# TC_PCB.net
KiCad netlist of a schematic drawn in Altium Designer
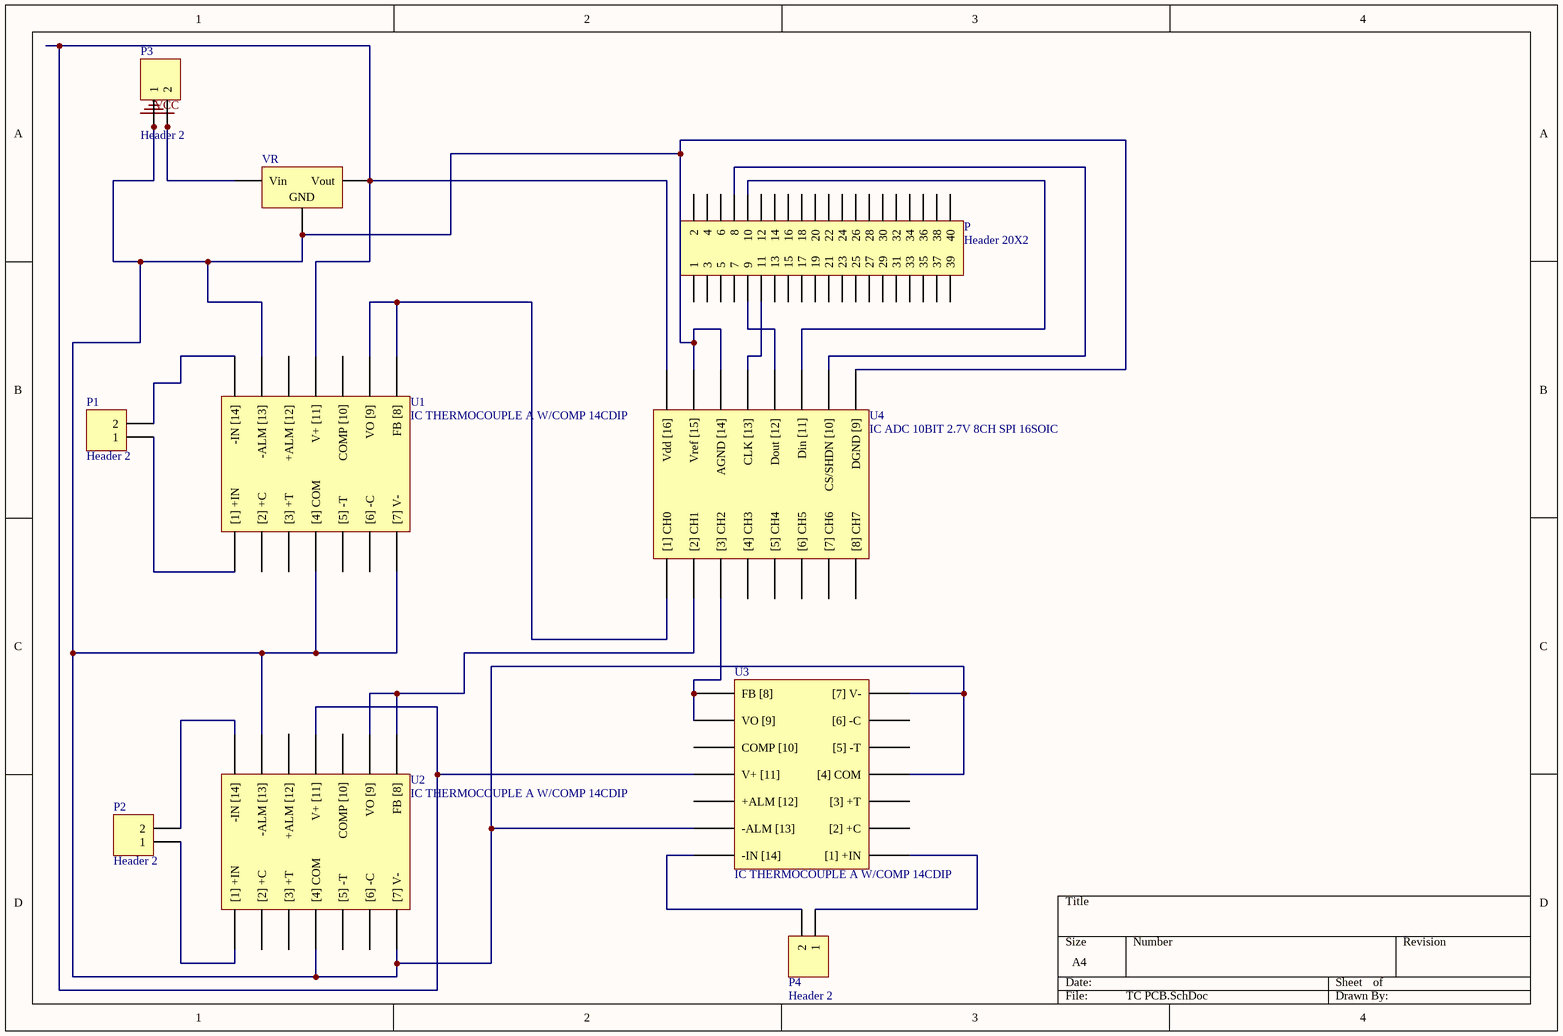
[diagram p0: TC PCB.SchDoc]

(export (version "E")
  (design (tool "Eeschema 10.0.6"))
  (components
    (comp (ref "P")
      (value "Header 20X2")
      (footprint "HDR2X20")
      (description "Header, 20-Pin, Dual row")
      (fields (field (name "PUBLISHER") "Altium Limited"))
      (libsource (lib "Miscellaneous Connectors") (part "Header 20X2"))
    )
    (comp (ref "P1")
      (value "Header 2")
      (footprint "HDR1X2")
      (description "Header, 2-Pin")
      (fields (field (name "PUBLISHER") "Altium Limited"))
      (libsource (lib "Miscellaneous Connectors") (part "Header 2"))
    )
    (comp (ref "P2")
      (value "Header 2")
      (footprint "HDR1X2")
      (description "Header, 2-Pin")
      (fields (field (name "PUBLISHER") "Altium Limited"))
      (libsource (lib "Miscellaneous Connectors") (part "Header 2"))
    )
    (comp (ref "P3")
      (value "Header 2")
      (footprint "HDR1X2")
      (description "Header, 2-Pin")
      (fields (field (name "PUBLISHER") "Altium Limited"))
      (libsource (lib "") (part "Header 2_1"))
    )
    (comp (ref "P4")
      (value "Header 2")
      (footprint "HDR1X2")
      (description "Header, 2-Pin")
      (fields (field (name "PUBLISHER") "Altium Limited"))
      (libsource (lib "") (part "Header 2_2"))
    )
    (comp (ref "U1")
      (value "IC THERMOCOUPLE A W/COMP 14CDIP")
      (footprint "IC THERMOCOUPLE A W/COMP 14CDIP")
      (libsource (lib "Main_Parts_Library") (part "IC THERMOCOUPLE A W/COMP 14CDIP"))
    )
    (comp (ref "U2")
      (value "IC THERMOCOUPLE A W/COMP 14CDIP")
      (footprint "IC THERMOCOUPLE A W/COMP 14CDIP")
      (libsource (lib "Main_Parts_Library") (part "IC THERMOCOUPLE A W/COMP 14CDIP"))
    )
    (comp (ref "U3")
      (value "IC THERMOCOUPLE A W/COMP 14CDIP")
      (footprint "IC THERMOCOUPLE A W/COMP 14CDIP")
      (libsource (lib "") (part "IC THERMOCOUPLE A W/COMP 14CDIP_1"))
    )
    (comp (ref "U4")
      (value "IC ADC 10BIT 2.7V 8CH SPI 16SOIC")
      (footprint "IC ADC 10BIT 2.7V 8CH SPI 16SOIC")
      (libsource (lib "Main_Parts_Library") (part "IC ADC 10BIT 2.7V 8CH SPI 16SOIC"))
    )
    (comp (ref "VR")
      (value "Volt Reg")
      (footprint "D2PAK_N")
      (description "Voltage Regulator")
      (fields (field (name "PUBLISHER") "Altium Limited"))
      (libsource (lib "Miscellaneous Devices") (part "Volt Reg"))
    )
  )
  (nets
    (net (code "1") (name "GND") (class "Default")
      (node (ref "P3") (pin "1") (pinfunction "1_1") (pintype "passive"))
      (node (ref "U1") (pin "13") (pinfunction "-ALM_[13]_13") (pintype "passive"))
      (node (ref "U1") (pin "4") (pinfunction "[4]_COM_4") (pintype "passive"))
      (node (ref "U1") (pin "7") (pinfunction "[7]_V-_7") (pintype "passive"))
      (node (ref "U2") (pin "13") (pinfunction "-ALM_[13]_13") (pintype "passive"))
      (node (ref "U2") (pin "4") (pinfunction "[4]_COM_4") (pintype "passive"))
      (node (ref "U2") (pin "7") (pinfunction "[7]_V-_7") (pintype "passive"))
      (node (ref "U3") (pin "13") (pinfunction "-ALM_[13]_13") (pintype "passive"))
      (node (ref "U3") (pin "4") (pinfunction "[4]_COM_4") (pintype "passive"))
      (node (ref "U3") (pin "7") (pinfunction "[7]_V-_7") (pintype "passive"))
      (node (ref "U4") (pin "14") (pinfunction "AGND_[14]_14") (pintype "passive"))
      (node (ref "U4") (pin "15") (pinfunction "Vref_[15]_15") (pintype "passive"))
      (node (ref "U4") (pin "9") (pinfunction "DGND_[9]_9") (pintype "passive"))
      (node (ref "VR") (pin "2") (pinfunction "GND_2") (pintype "passive"))
    )
    (net (code "2") (name "Net-(U1--IN_[14])") (class "Default")
      (node (ref "P1") (pin "2") (pinfunction "2_2") (pintype "passive"))
      (node (ref "U1") (pin "14") (pinfunction "-IN_[14]_14") (pintype "passive"))
    )
    (net (code "3") (name "Net-(U1-FB_[8])") (class "Default")
      (node (ref "U1") (pin "8") (pinfunction "FB_[8]_8") (pintype "passive"))
      (node (ref "U1") (pin "9") (pinfunction "VO_[9]_9") (pintype "passive"))
      (node (ref "U4") (pin "1") (pinfunction "[1]_CH0_1") (pintype "passive"))
    )
    (net (code "4") (name "Net-(U1-V+_[11])") (class "Default")
      (node (ref "U1") (pin "11") (pinfunction "V+_[11]_11") (pintype "passive"))
      (node (ref "U2") (pin "11") (pinfunction "V+_[11]_11") (pintype "passive"))
      (node (ref "U3") (pin "11") (pinfunction "V+_[11]_11") (pintype "passive"))
      (node (ref "U4") (pin "16") (pinfunction "Vdd_[16]_16") (pintype "passive"))
      (node (ref "VR") (pin "3") (pinfunction "Vout_3") (pintype "passive"))
    )
    (net (code "5") (name "Net-(U1-[1]_+IN)") (class "Default")
      (node (ref "P1") (pin "1") (pinfunction "1_1") (pintype "passive"))
      (node (ref "U1") (pin "1") (pinfunction "[1]_+IN_1") (pintype "passive"))
    )
    (net (code "6") (name "Net-(U2--IN_[14])") (class "Default")
      (node (ref "P2") (pin "2") (pinfunction "2_2") (pintype "passive"))
      (node (ref "U2") (pin "14") (pinfunction "-IN_[14]_14") (pintype "passive"))
    )
    (net (code "7") (name "Net-(U2-FB_[8])") (class "Default")
      (node (ref "U2") (pin "8") (pinfunction "FB_[8]_8") (pintype "passive"))
      (node (ref "U2") (pin "9") (pinfunction "VO_[9]_9") (pintype "passive"))
      (node (ref "U4") (pin "2") (pinfunction "[2]_CH1_2") (pintype "passive"))
    )
    (net (code "8") (name "Net-(U2-[1]_+IN)") (class "Default")
      (node (ref "P2") (pin "1") (pinfunction "1_1") (pintype "passive"))
      (node (ref "U2") (pin "1") (pinfunction "[1]_+IN_1") (pintype "passive"))
    )
    (net (code "9") (name "Net-(U3--IN_[14])") (class "Default")
      (node (ref "P4") (pin "2") (pinfunction "2_2") (pintype "passive"))
      (node (ref "U3") (pin "14") (pinfunction "-IN_[14]_14") (pintype "passive"))
    )
    (net (code "10") (name "Net-(U3-FB_[8])") (class "Default")
      (node (ref "U3") (pin "8") (pinfunction "FB_[8]_8") (pintype "passive"))
      (node (ref "U3") (pin "9") (pinfunction "VO_[9]_9") (pintype "passive"))
      (node (ref "U4") (pin "3") (pinfunction "[3]_CH2_3") (pintype "passive"))
    )
    (net (code "11") (name "Net-(U3-[1]_+IN)") (class "Default")
      (node (ref "P4") (pin "1") (pinfunction "1_1") (pintype "passive"))
      (node (ref "U3") (pin "1") (pinfunction "[1]_+IN_1") (pintype "passive"))
    )
    (net (code "12") (name "Net-(U4-CLK_[13])") (class "Default")
      (node (ref "P") (pin "11") (pinfunction "11_11") (pintype "passive"))
      (node (ref "U4") (pin "13") (pinfunction "CLK_[13]_13") (pintype "passive"))
    )
    (net (code "13") (name "Net-(U4-CS{slash}SHDN_[10])") (class "Default")
      (node (ref "P") (pin "8") (pinfunction "8_8") (pintype "passive"))
      (node (ref "U4") (pin "10") (pinfunction "CS/SHDN_[10]_10") (pintype "passive"))
    )
    (net (code "14") (name "Net-(U4-Din_[11])") (class "Default")
      (node (ref "P") (pin "10") (pinfunction "10_10") (pintype "passive"))
      (node (ref "U4") (pin "11") (pinfunction "Din_[11]_11") (pintype "passive"))
    )
    (net (code "15") (name "Net-(U4-Dout_[12])") (class "Default")
      (node (ref "P") (pin "9") (pinfunction "9_9") (pintype "passive"))
      (node (ref "U4") (pin "12") (pinfunction "Dout_[12]_12") (pintype "passive"))
    )
    (net (code "16") (name "VCC") (class "Default")
      (node (ref "P3") (pin "2") (pinfunction "2_2") (pintype "passive"))
      (node (ref "VR") (pin "1") (pinfunction "Vin_1") (pintype "passive"))
    )
    (net (code "17") (name "unconnected-(P-Pad1)") (class "Default")
      (node (ref "P") (pin "1") (pinfunction "1_1") (pintype "passive"))
    )
    (net (code "18") (name "unconnected-(P-Pad2)") (class "Default")
      (node (ref "P") (pin "2") (pinfunction "2_2") (pintype "passive"))
    )
    (net (code "19") (name "unconnected-(P-Pad3)") (class "Default")
      (node (ref "P") (pin "3") (pinfunction "3_3") (pintype "passive"))
    )
    (net (code "20") (name "unconnected-(P-Pad4)") (class "Default")
      (node (ref "P") (pin "4") (pinfunction "4_4") (pintype "passive"))
    )
    (net (code "21") (name "unconnected-(P-Pad5)") (class "Default")
      (node (ref "P") (pin "5") (pinfunction "5_5") (pintype "passive"))
    )
    (net (code "22") (name "unconnected-(P-Pad6)") (class "Default")
      (node (ref "P") (pin "6") (pinfunction "6_6") (pintype "passive"))
    )
    (net (code "23") (name "unconnected-(P-Pad7)") (class "Default")
      (node (ref "P") (pin "7") (pinfunction "7_7") (pintype "passive"))
    )
    (net (code "24") (name "unconnected-(P-Pad12)") (class "Default")
      (node (ref "P") (pin "12") (pinfunction "12_12") (pintype "passive"))
    )
    (net (code "25") (name "unconnected-(P-Pad13)") (class "Default")
      (node (ref "P") (pin "13") (pinfunction "13_13") (pintype "passive"))
    )
    (net (code "26") (name "unconnected-(P-Pad14)") (class "Default")
      (node (ref "P") (pin "14") (pinfunction "14_14") (pintype "passive"))
    )
    (net (code "27") (name "unconnected-(P-Pad15)") (class "Default")
      (node (ref "P") (pin "15") (pinfunction "15_15") (pintype "passive"))
    )
    (net (code "28") (name "unconnected-(P-Pad16)") (class "Default")
      (node (ref "P") (pin "16") (pinfunction "16_16") (pintype "passive"))
    )
    (net (code "29") (name "unconnected-(P-Pad17)") (class "Default")
      (node (ref "P") (pin "17") (pinfunction "17_17") (pintype "passive"))
    )
    (net (code "30") (name "unconnected-(P-Pad18)") (class "Default")
      (node (ref "P") (pin "18") (pinfunction "18_18") (pintype "passive"))
    )
    (net (code "31") (name "unconnected-(P-Pad19)") (class "Default")
      (node (ref "P") (pin "19") (pinfunction "19_19") (pintype "passive"))
    )
    (net (code "32") (name "unconnected-(P-Pad20)") (class "Default")
      (node (ref "P") (pin "20") (pinfunction "20_20") (pintype "passive"))
    )
    (net (code "33") (name "unconnected-(P-Pad21)") (class "Default")
      (node (ref "P") (pin "21") (pinfunction "21_21") (pintype "passive"))
    )
    (net (code "34") (name "unconnected-(P-Pad22)") (class "Default")
      (node (ref "P") (pin "22") (pinfunction "22_22") (pintype "passive"))
    )
    (net (code "35") (name "unconnected-(P-Pad23)") (class "Default")
      (node (ref "P") (pin "23") (pinfunction "23_23") (pintype "passive"))
    )
    (net (code "36") (name "unconnected-(P-Pad24)") (class "Default")
      (node (ref "P") (pin "24") (pinfunction "24_24") (pintype "passive"))
    )
    (net (code "37") (name "unconnected-(P-Pad25)") (class "Default")
      (node (ref "P") (pin "25") (pinfunction "25_25") (pintype "passive"))
    )
    (net (code "38") (name "unconnected-(P-Pad26)") (class "Default")
      (node (ref "P") (pin "26") (pinfunction "26_26") (pintype "passive"))
    )
    (net (code "39") (name "unconnected-(P-Pad27)") (class "Default")
      (node (ref "P") (pin "27") (pinfunction "27_27") (pintype "passive"))
    )
    (net (code "40") (name "unconnected-(P-Pad28)") (class "Default")
      (node (ref "P") (pin "28") (pinfunction "28_28") (pintype "passive"))
    )
    (net (code "41") (name "unconnected-(P-Pad29)") (class "Default")
      (node (ref "P") (pin "29") (pinfunction "29_29") (pintype "passive"))
    )
    (net (code "42") (name "unconnected-(P-Pad30)") (class "Default")
      (node (ref "P") (pin "30") (pinfunction "30_30") (pintype "passive"))
    )
    (net (code "43") (name "unconnected-(P-Pad31)") (class "Default")
      (node (ref "P") (pin "31") (pinfunction "31_31") (pintype "passive"))
    )
    (net (code "44") (name "unconnected-(P-Pad32)") (class "Default")
      (node (ref "P") (pin "32") (pinfunction "32_32") (pintype "passive"))
    )
    (net (code "45") (name "unconnected-(P-Pad33)") (class "Default")
      (node (ref "P") (pin "33") (pinfunction "33_33") (pintype "passive"))
    )
    (net (code "46") (name "unconnected-(P-Pad34)") (class "Default")
      (node (ref "P") (pin "34") (pinfunction "34_34") (pintype "passive"))
    )
    (net (code "47") (name "unconnected-(P-Pad35)") (class "Default")
      (node (ref "P") (pin "35") (pinfunction "35_35") (pintype "passive"))
    )
    (net (code "48") (name "unconnected-(P-Pad36)") (class "Default")
      (node (ref "P") (pin "36") (pinfunction "36_36") (pintype "passive"))
    )
    (net (code "49") (name "unconnected-(P-Pad37)") (class "Default")
      (node (ref "P") (pin "37") (pinfunction "37_37") (pintype "passive"))
    )
    (net (code "50") (name "unconnected-(P-Pad38)") (class "Default")
      (node (ref "P") (pin "38") (pinfunction "38_38") (pintype "passive"))
    )
    (net (code "51") (name "unconnected-(P-Pad39)") (class "Default")
      (node (ref "P") (pin "39") (pinfunction "39_39") (pintype "passive"))
    )
    (net (code "52") (name "unconnected-(P-Pad40)") (class "Default")
      (node (ref "P") (pin "40") (pinfunction "40_40") (pintype "passive"))
    )
    (net (code "53") (name "unconnected-(U1-+ALM_[12]-Pad12)") (class "Default")
      (node (ref "U1") (pin "12") (pinfunction "+ALM_[12]_12") (pintype "passive"))
    )
    (net (code "54") (name "unconnected-(U1-COMP_[10]-Pad10)") (class "Default")
      (node (ref "U1") (pin "10") (pinfunction "COMP_[10]_10") (pintype "passive"))
    )
    (net (code "55") (name "unconnected-(U1-[2]_+C-Pad2)") (class "Default")
      (node (ref "U1") (pin "2") (pinfunction "[2]_+C_2") (pintype "passive"))
    )
    (net (code "56") (name "unconnected-(U1-[3]_+T-Pad3)") (class "Default")
      (node (ref "U1") (pin "3") (pinfunction "[3]_+T_3") (pintype "passive"))
    )
    (net (code "57") (name "unconnected-(U1-[5]_-T-Pad5)") (class "Default")
      (node (ref "U1") (pin "5") (pinfunction "[5]_-T_5") (pintype "passive"))
    )
    (net (code "58") (name "unconnected-(U1-[6]_-C-Pad6)") (class "Default")
      (node (ref "U1") (pin "6") (pinfunction "[6]_-C_6") (pintype "passive"))
    )
    (net (code "59") (name "unconnected-(U2-+ALM_[12]-Pad12)") (class "Default")
      (node (ref "U2") (pin "12") (pinfunction "+ALM_[12]_12") (pintype "passive"))
    )
    (net (code "60") (name "unconnected-(U2-COMP_[10]-Pad10)") (class "Default")
      (node (ref "U2") (pin "10") (pinfunction "COMP_[10]_10") (pintype "passive"))
    )
    (net (code "61") (name "unconnected-(U2-[2]_+C-Pad2)") (class "Default")
      (node (ref "U2") (pin "2") (pinfunction "[2]_+C_2") (pintype "passive"))
    )
    (net (code "62") (name "unconnected-(U2-[3]_+T-Pad3)") (class "Default")
      (node (ref "U2") (pin "3") (pinfunction "[3]_+T_3") (pintype "passive"))
    )
    (net (code "63") (name "unconnected-(U2-[5]_-T-Pad5)") (class "Default")
      (node (ref "U2") (pin "5") (pinfunction "[5]_-T_5") (pintype "passive"))
    )
    (net (code "64") (name "unconnected-(U2-[6]_-C-Pad6)") (class "Default")
      (node (ref "U2") (pin "6") (pinfunction "[6]_-C_6") (pintype "passive"))
    )
    (net (code "65") (name "unconnected-(U3-+ALM_[12]-Pad12)") (class "Default")
      (node (ref "U3") (pin "12") (pinfunction "+ALM_[12]_12") (pintype "passive"))
    )
    (net (code "66") (name "unconnected-(U3-COMP_[10]-Pad10)") (class "Default")
      (node (ref "U3") (pin "10") (pinfunction "COMP_[10]_10") (pintype "passive"))
    )
    (net (code "67") (name "unconnected-(U3-[2]_+C-Pad2)") (class "Default")
      (node (ref "U3") (pin "2") (pinfunction "[2]_+C_2") (pintype "passive"))
    )
    (net (code "68") (name "unconnected-(U3-[3]_+T-Pad3)") (class "Default")
      (node (ref "U3") (pin "3") (pinfunction "[3]_+T_3") (pintype "passive"))
    )
    (net (code "69") (name "unconnected-(U3-[5]_-T-Pad5)") (class "Default")
      (node (ref "U3") (pin "5") (pinfunction "[5]_-T_5") (pintype "passive"))
    )
    (net (code "70") (name "unconnected-(U3-[6]_-C-Pad6)") (class "Default")
      (node (ref "U3") (pin "6") (pinfunction "[6]_-C_6") (pintype "passive"))
    )
    (net (code "71") (name "unconnected-(U4-[4]_CH3-Pad4)") (class "Default")
      (node (ref "U4") (pin "4") (pinfunction "[4]_CH3_4") (pintype "passive"))
    )
    (net (code "72") (name "unconnected-(U4-[5]_CH4-Pad5)") (class "Default")
      (node (ref "U4") (pin "5") (pinfunction "[5]_CH4_5") (pintype "passive"))
    )
    (net (code "73") (name "unconnected-(U4-[6]_CH5-Pad6)") (class "Default")
      (node (ref "U4") (pin "6") (pinfunction "[6]_CH5_6") (pintype "passive"))
    )
    (net (code "74") (name "unconnected-(U4-[7]_CH6-Pad7)") (class "Default")
      (node (ref "U4") (pin "7") (pinfunction "[7]_CH6_7") (pintype "passive"))
    )
    (net (code "75") (name "unconnected-(U4-[8]_CH7-Pad8)") (class "Default")
      (node (ref "U4") (pin "8") (pinfunction "[8]_CH7_8") (pintype "passive"))
    )
  )
)
